# SSRT_Tronics.net
KiCad netlist of a schematic drawn in Altium Designer
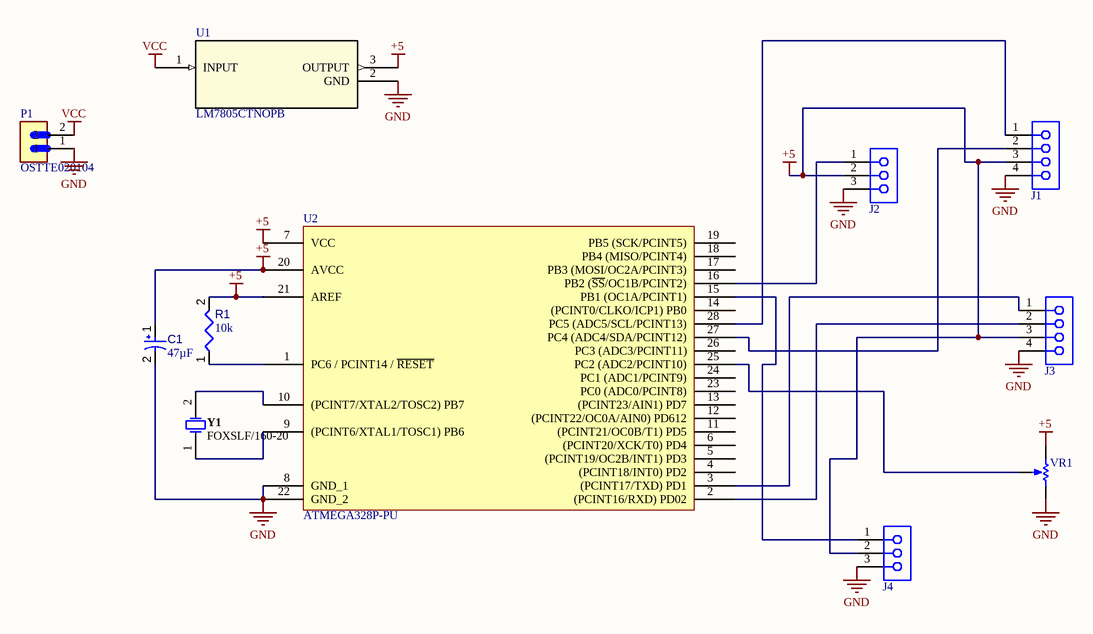
[diagram p0: SSRT Tronics.SchDoc]

(export (version "E")
  (design (tool "Eeschema 10.0.6"))
  (components
    (comp (ref "C1")
      (value "47µF")
      (footprint "CAPPR55-250-1120X630X1220")
      (description "Aluminum Electrolytic Capacitor, 47 uF, +/-20%, 50 V, -40 to 85 degC, 2-Pin THD, RoHS, Bulk")
      (fields (field (name "TOLERANCE") "20%") (field (name "MANUFACTURER") "Panasonic"))
      (libsource (lib "Senuda Ratnayake") (part "CAP-P-2"))
    )
    (comp (ref "J1")
      (value "61300411821")
      (footprint "61300411821")
      (description "WR-PHD Socket Header, THT, Vertical, pitch 2.54mm, 1 Row, 4P")
      (fields (field (name "MANUFACTURER") "Wurth Elektronik"))
      (libsource (lib "WR-PHD") (part "61300411821"))
    )
    (comp (ref "J2")
      (value "61300311821")
      (footprint "61300311821")
      (description "WR-PHD Socket Header, THT, Vertical, pitch 2.54mm, 1 Row, 3P")
      (fields (field (name "MANUFACTURER") "Wurth Elektronik"))
      (libsource (lib "WR-PHD") (part "61300311821"))
    )
    (comp (ref "J3")
      (value "61300411821")
      (footprint "61300411821")
      (description "WR-PHD Socket Header, THT, Vertical, pitch 2.54mm, 1 Row, 4P")
      (fields (field (name "MANUFACTURER") "Wurth Elektronik"))
      (libsource (lib "WR-PHD") (part "61300411821"))
    )
    (comp (ref "J4")
      (value "61300311821")
      (footprint "61300311821")
      (description "WR-PHD Socket Header, THT, Vertical, pitch 2.54mm, 1 Row, 3P")
      (fields (field (name "MANUFACTURER") "Wurth Elektronik"))
      (libsource (lib "WR-PHD") (part "61300311821"))
    )
    (comp (ref "P1")
      (value "OSTTE020104")
      (footprint "OST_OSTTE020104")
      (description "2 Position Wire to Board Terminal Block Horizontal with Board 0.138 (3.50mm) Through Hole")
      (fields (field (name "MF") "On Shore"))
      (libsource (lib "OSTTE020104") (part "OSTTE020104"))
    )
    (comp (ref "R1")
      (value "10k")
      (footprint "RESA60-630X240")
      (description "Axial Resistor, 10 KOhm, +/- 1%, 0.25 W, -55 to 155 degC, 2-Pin THD, RoHS, Bulk")
      (fields (field (name "TOLERANCE") "1%") (field (name "POWER") "250mW"))
      (libsource (lib "Senuda Ratnayake") (part "RES-2"))
    )
    (comp (ref "U1")
      (value "LM7805CTNOPB")
      (footprint "NDE3_TEX")
      (description "No Description Available")
      (libsource (lib "LM7805CTNOPB") (part "LM7805CTNOPB"))
    )
    (comp (ref "U2")
      (value "ATMEGA328P-PU")
      (footprint "27_DIP_7.62mm")
      (description "ATMEGA328P-PU; 8 bit Microcontroller AVR 20MHz 1; 32kb Flash; 2kb RAM; I2C SPI 2")
      (fields (field (name "MANUFACTURER") "Microchip / Atmel"))
      (libsource (lib "ATMEGA328P-PU") (part "ATMEGA328P-PU"))
    )
    (comp (ref "VR1")
      (value "3296W-1-103LF")
      (footprint "BOUR-3296W")
      (fields
        (field (name "TOLERANCE") "10%")
        (field (name "POWER") "500mW")
        (field (name "MANUFACTURER") "Bourns")
      )
      (libsource (lib "Senuda Ratnayake") (part "RES-POT-3"))
    )
    (comp (ref "Y1")
      (value "FOXSLF/160-20")
      (footprint "FOX-FOXSLF160-20")
      (fields (field (name "MANUFACTURER") "FOX Electronics") (field (name "TOLERANCE") "50ppm"))
      (libsource (lib "Senuda Ratnayake") (part "XTAL-1-2-2"))
    )
  )
  (nets
    (net (code "1") (name "+5") (class "Default")
      (node (ref "C1") (pin "1") (pinfunction "1_1") (pintype "passive"))
      (node (ref "J1") (pin "3") (pinfunction "3_3") (pintype "passive"))
      (node (ref "J2") (pin "2") (pinfunction "2_2") (pintype "passive"))
      (node (ref "J3") (pin "3") (pinfunction "3_3") (pintype "passive"))
      (node (ref "J4") (pin "2") (pinfunction "2_2") (pintype "passive"))
      (node (ref "R1") (pin "2") (pinfunction "2_2") (pintype "passive"))
      (node (ref "U1") (pin "3") (pinfunction "OUTPUT_3") (pintype "output"))
      (node (ref "U2") (pin "20") (pinfunction "AVCC_20") (pintype "passive"))
      (node (ref "U2") (pin "21") (pinfunction "AREF_21") (pintype "passive"))
      (node (ref "U2") (pin "7") (pinfunction "VCC_7") (pintype "passive"))
      (node (ref "VR1") (pin "1") (pinfunction "CCW_1") (pintype "passive"))
    )
    (net (code "2") (name "GND") (class "Default")
      (node (ref "C1") (pin "2") (pinfunction "2_2") (pintype "passive"))
      (node (ref "J1") (pin "4") (pinfunction "4_4") (pintype "passive"))
      (node (ref "J2") (pin "3") (pinfunction "3_3") (pintype "passive"))
      (node (ref "J3") (pin "4") (pinfunction "4_4") (pintype "passive"))
      (node (ref "J4") (pin "3") (pinfunction "3_3") (pintype "passive"))
      (node (ref "P1") (pin "1") (pinfunction "1_1") (pintype "passive"))
      (node (ref "U1") (pin "2") (pinfunction "GND_2") (pintype "power_in"))
      (node (ref "U2") (pin "22") (pinfunction "GND_2_22") (pintype "passive"))
      (node (ref "U2") (pin "8") (pinfunction "GND_1_8") (pintype "passive"))
      (node (ref "VR1") (pin "3") (pinfunction "CW_3") (pintype "passive"))
    )
    (net (code "3") (name "Net-(U2-(PCINT6{slash}XTAL1{slash}TOSC1)_PB6)") (class "Default")
      (node (ref "U2") (pin "9") (pinfunction "(PCINT6/XTAL1/TOSC1)_PB6_9") (pintype "passive"))
      (node (ref "Y1") (pin "1") (pinfunction "1_1") (pintype "passive"))
    )
    (net (code "4") (name "Net-(U2-(PCINT7{slash}XTAL2{slash}TOSC2)_PB7)") (class "Default")
      (node (ref "U2") (pin "10") (pinfunction "(PCINT7/XTAL2/TOSC2)_PB7_10") (pintype "passive"))
      (node (ref "Y1") (pin "2") (pinfunction "2_2") (pintype "passive"))
    )
    (net (code "5") (name "Net-(U2-(PCINT16{slash}RXD)_PD02)") (class "Default")
      (node (ref "J3") (pin "2") (pinfunction "2_2") (pintype "passive"))
      (node (ref "U2") (pin "2") (pinfunction "(PCINT16/RXD)_PD02_2") (pintype "passive"))
    )
    (net (code "6") (name "Net-(U2-(PCINT17{slash}TXD)_PD1)") (class "Default")
      (node (ref "J3") (pin "1") (pinfunction "1_1") (pintype "passive"))
      (node (ref "U2") (pin "3") (pinfunction "(PCINT17/TXD)_PD1_3") (pintype "passive"))
    )
    (net (code "7") (name "Net-(U2-PB1_(OC1A{slash}PCINT1))") (class "Default")
      (node (ref "J4") (pin "1") (pinfunction "1_1") (pintype "passive"))
      (node (ref "U2") (pin "15") (pinfunction "PB1_(OC1A/PCINT1)_15") (pintype "passive"))
    )
    (net (code "8") (name "Net-(U2-PB2_(~{SS}{slash}OC1B{slash}PCINT2))") (class "Default")
      (node (ref "J2") (pin "1") (pinfunction "1_1") (pintype "passive"))
      (node (ref "U2") (pin "16") (pinfunction "PB2_(~{SS}/OC1B/PCINT2)_16") (pintype "passive"))
    )
    (net (code "9") (name "Net-(U2-PC2_(ADC2{slash}PCINT10))") (class "Default")
      (node (ref "U2") (pin "25") (pinfunction "PC2_(ADC2/PCINT10)_25") (pintype "passive"))
      (node (ref "VR1") (pin "2") (pinfunction "S_2") (pintype "passive"))
    )
    (net (code "10") (name "Net-(U2-PC4_(ADC4{slash}SDA{slash}PCINT12))") (class "Default")
      (node (ref "J1") (pin "2") (pinfunction "2_2") (pintype "passive"))
      (node (ref "U2") (pin "27") (pinfunction "PC4_(ADC4/SDA/PCINT12)_27") (pintype "passive"))
    )
    (net (code "11") (name "Net-(U2-PC5_(ADC5{slash}SCL{slash}PCINT13))") (class "Default")
      (node (ref "J1") (pin "1") (pinfunction "1_1") (pintype "passive"))
      (node (ref "U2") (pin "28") (pinfunction "PC5_(ADC5/SCL/PCINT13)_28") (pintype "passive"))
    )
    (net (code "12") (name "Net-(U2-PC6_{slash}_PCINT14_{slash}_~{RESET})") (class "Default")
      (node (ref "R1") (pin "1") (pinfunction "1_1") (pintype "passive"))
      (node (ref "U2") (pin "1") (pinfunction "PC6_/_PCINT14_/_~{RESET}_1") (pintype "passive"))
    )
    (net (code "13") (name "VCC") (class "Default")
      (node (ref "P1") (pin "2") (pinfunction "2_2") (pintype "passive"))
      (node (ref "U1") (pin "1") (pinfunction "INPUT_1") (pintype "input"))
    )
    (net (code "14") (name "unconnected-(U2-(PCINT0{slash}CLKO{slash}ICP1)_PB0-Pad14)") (class "Default")
      (node (ref "U2") (pin "14") (pinfunction "(PCINT0/CLKO/ICP1)_PB0_14") (pintype "passive"))
    )
    (net (code "15") (name "unconnected-(U2-(PCINT18{slash}INT0)_PD2-Pad4)") (class "Default")
      (node (ref "U2") (pin "4") (pinfunction "(PCINT18/INT0)_PD2_4") (pintype "passive"))
    )
    (net (code "16") (name "unconnected-(U2-(PCINT19{slash}OC2B{slash}INT1)_PD3-Pad5)") (class "Default")
      (node (ref "U2") (pin "5") (pinfunction "(PCINT19/OC2B/INT1)_PD3_5") (pintype "passive"))
    )
    (net (code "17") (name "unconnected-(U2-(PCINT20{slash}XCK{slash}T0)_PD4-Pad6)") (class "Default")
      (node (ref "U2") (pin "6") (pinfunction "(PCINT20/XCK/T0)_PD4_6") (pintype "passive"))
    )
    (net (code "18") (name "unconnected-(U2-(PCINT21{slash}OC0B{slash}T1)_PD5-Pad11)") (class "Default")
      (node (ref "U2") (pin "11") (pinfunction "(PCINT21/OC0B/T1)_PD5_11") (pintype "passive"))
    )
    (net (code "19") (name "unconnected-(U2-(PCINT22{slash}OC0A{slash}AIN0)_PD612-Pad12)") (class "Default")
      (node (ref "U2") (pin "12") (pinfunction "(PCINT22/OC0A/AIN0)_PD612_12") (pintype "passive"))
    )
    (net (code "20") (name "unconnected-(U2-(PCINT23{slash}AIN1)_PD7-Pad13)") (class "Default")
      (node (ref "U2") (pin "13") (pinfunction "(PCINT23/AIN1)_PD7_13") (pintype "passive"))
    )
    (net (code "21") (name "unconnected-(U2-PB3_(MOSI{slash}OC2A{slash}PCINT3)-Pad17)") (class "Default")
      (node (ref "U2") (pin "17") (pinfunction "PB3_(MOSI/OC2A/PCINT3)_17") (pintype "passive"))
    )
    (net (code "22") (name "unconnected-(U2-PB4_(MISO{slash}PCINT4)-Pad18)") (class "Default")
      (node (ref "U2") (pin "18") (pinfunction "PB4_(MISO/PCINT4)_18") (pintype "passive"))
    )
    (net (code "23") (name "unconnected-(U2-PB5_(SCK{slash}PCINT5)-Pad19)") (class "Default")
      (node (ref "U2") (pin "19") (pinfunction "PB5_(SCK/PCINT5)_19") (pintype "passive"))
    )
    (net (code "24") (name "unconnected-(U2-PC0_(ADC0{slash}PCINT8)-Pad23)") (class "Default")
      (node (ref "U2") (pin "23") (pinfunction "PC0_(ADC0/PCINT8)_23") (pintype "passive"))
    )
    (net (code "25") (name "unconnected-(U2-PC1_(ADC1{slash}PCINT9)-Pad24)") (class "Default")
      (node (ref "U2") (pin "24") (pinfunction "PC1_(ADC1/PCINT9)_24") (pintype "passive"))
    )
    (net (code "26") (name "unconnected-(U2-PC3_(ADC3{slash}PCINT11)-Pad26)") (class "Default")
      (node (ref "U2") (pin "26") (pinfunction "PC3_(ADC3/PCINT11)_26") (pintype "passive"))
    )
  )
)
